# Sheet1.net
KiCad netlist of a schematic drawn in Altium Designer
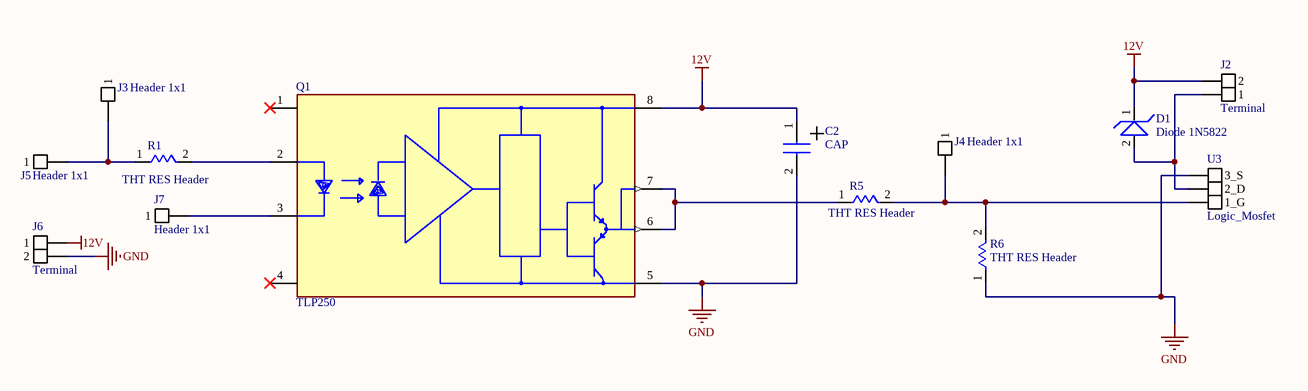
[diagram p0: Sheet1.SchDoc]

(export (version "E")
  (design (tool "Eeschema 10.0.6"))
  (components
    (comp (ref "C2")
      (value "CAP")
      (footprint "Cap 5x10")
      (description "Capacitor")
      (libsource (lib "Sonar_Gonderici_Schlib1") (part "CAP"))
    )
    (comp (ref "D1")
      (value "Diode 1N5822")
      (footprint "Diode")
      (description "SS34 1N5822 SMD Schottky Diode 3A 40V")
      (libsource (lib "Sonar_Gonderici_Schlib1") (part "Diode 1N5822 SMD"))
    )
    (comp (ref "J2")
      (value "Terminal")
      (footprint "Terminal")
      (libsource (lib "Sonar_Gonderici_Schlib1") (part "Terminal"))
    )
    (comp (ref "J3")
      (value "Header 1x1")
      (footprint "Header 1x1")
      (description "Header")
      (libsource (lib "Sonar_Gonderici_Schlib1") (part "Header 1x1"))
    )
    (comp (ref "J4")
      (value "Header 1x1")
      (footprint "Header 1x1")
      (description "Header")
      (libsource (lib "Sonar_Gonderici_Schlib1") (part "Header 1x1"))
    )
    (comp (ref "J5")
      (value "Header 1x1")
      (footprint "Header 1x1")
      (description "Header")
      (libsource (lib "Sonar_Gonderici_Schlib1") (part "Header 1x1"))
    )
    (comp (ref "J6")
      (value "Terminal")
      (footprint "Terminal")
      (libsource (lib "Sonar_Gonderici_Schlib1") (part "Terminal"))
    )
    (comp (ref "J7")
      (value "Header 1x1")
      (footprint "Header 1x1")
      (description "Header")
      (libsource (lib "Sonar_Gonderici_Schlib1") (part "Header 1x1"))
    )
    (comp (ref "Q1")
      (value "TLP250")
      (footprint "FP-11-10C4-MFG")
      (description "Optocoupler Drive Push-Pull 1-CH 30V 600V 8-Pin PDIP")
      (fields
        (field (name "MANUFACTURER") "TOSHIBA")
        (field (name "OCTOPART") "https://octopart.com/tlp-250-toshiba-99104964")
      )
      (libsource (lib "Sonar_Gonderici_Schlib1") (part "CMP-35887-000009-1"))
    )
    (comp (ref "R1")
      (value "THT RES Header")
      (footprint "Res")
      (description "THT RES")
      (libsource (lib "Sonar_Gonderici_Schlib1") (part "THT RES Header"))
    )
    (comp (ref "R5")
      (value "THT RES Header")
      (footprint "Res")
      (description "THT RES")
      (libsource (lib "Sonar_Gonderici_Schlib1") (part "THT RES Header"))
    )
    (comp (ref "R6")
      (value "THT RES Header")
      (footprint "Res")
      (description "THT RES")
      (libsource (lib "Sonar_Gonderici_Schlib1") (part "THT RES Header"))
    )
    (comp (ref "U3")
      (value "Logic_Mosfet")
      (footprint "Logic_Mosfet")
      (libsource (lib "Sonar_Gonderici_Schlib1") (part "Logic_Mosfet"))
    )
  )
  (nets
    (net (code "1") (name "12V") (class "Default")
      (node (ref "C2") (pin "1") (pinfunction "1_1") (pintype "passive"))
      (node (ref "D1") (pin "1") (pinfunction "1_1") (pintype "passive"))
      (node (ref "J2") (pin "2") (pinfunction "2_2") (pintype "passive"))
      (node (ref "J6") (pin "1") (pinfunction "1_1") (pintype "passive"))
      (node (ref "Q1") (pin "8") (pinfunction "VCC_8") (pintype "power_in"))
    )
    (net (code "2") (name "GND") (class "Default")
      (node (ref "C2") (pin "2") (pinfunction "2_2") (pintype "passive"))
      (node (ref "J6") (pin "2") (pinfunction "2_2") (pintype "passive"))
      (node (ref "Q1") (pin "5") (pinfunction "GND_5") (pintype "power_in"))
      (node (ref "R6") (pin "1") (pinfunction "1_1") (pintype "passive"))
      (node (ref "U3") (pin "3") (pinfunction "3_S_3") (pintype "passive"))
    )
    (net (code "3") (name "Net-(J3-Pad1)") (class "Default")
      (node (ref "J3") (pin "1") (pinfunction "1_1") (pintype "passive"))
      (node (ref "J5") (pin "1") (pinfunction "1_1") (pintype "passive"))
      (node (ref "R1") (pin "1") (pinfunction "1_1") (pintype "passive"))
    )
    (net (code "4") (name "Net-(Q1-A)") (class "Default")
      (node (ref "Q1") (pin "2") (pinfunction "A_2") (pintype "passive"))
      (node (ref "R1") (pin "2") (pinfunction "2_2") (pintype "passive"))
    )
    (net (code "5") (name "Net-(Q1-C)") (class "Default")
      (node (ref "J7") (pin "1") (pinfunction "1_1") (pintype "passive"))
      (node (ref "Q1") (pin "3") (pinfunction "C_3") (pintype "passive"))
    )
    (net (code "6") (name "Net-(Q1-VO(Output))") (class "Default")
      (node (ref "Q1") (pin "6") (pinfunction "VO(Output)_6") (pintype "output"))
      (node (ref "Q1") (pin "7") (pinfunction "VO_7") (pintype "output"))
      (node (ref "R5") (pin "1") (pinfunction "1_1") (pintype "passive"))
    )
    (net (code "7") (name "Net-(U3-1_G)") (class "Default")
      (node (ref "J4") (pin "1") (pinfunction "1_1") (pintype "passive"))
      (node (ref "R5") (pin "2") (pinfunction "2_2") (pintype "passive"))
      (node (ref "R6") (pin "2") (pinfunction "2_2") (pintype "passive"))
      (node (ref "U3") (pin "1") (pinfunction "1_G_1") (pintype "passive"))
    )
    (net (code "8") (name "Net-(U3-2_D)") (class "Default")
      (node (ref "D1") (pin "2") (pinfunction "2_2") (pintype "passive"))
      (node (ref "J2") (pin "1") (pinfunction "1_1") (pintype "passive"))
      (node (ref "U3") (pin "2") (pinfunction "2_D_2") (pintype "passive"))
    )
    (net (code "9") (name "unconnected-(Q1-NC-Pad1)") (class "Default")
      (node (ref "Q1") (pin "1") (pinfunction "NC_1") (pintype "passive+no_connect"))
    )
    (net (code "10") (name "unconnected-(Q1-NC-Pad4)") (class "Default")
      (node (ref "Q1") (pin "4") (pinfunction "NC_4") (pintype "passive+no_connect"))
    )
  )
)
